# Page_5_DDR.net
KiCad netlist of a schematic drawn in Altium Designer
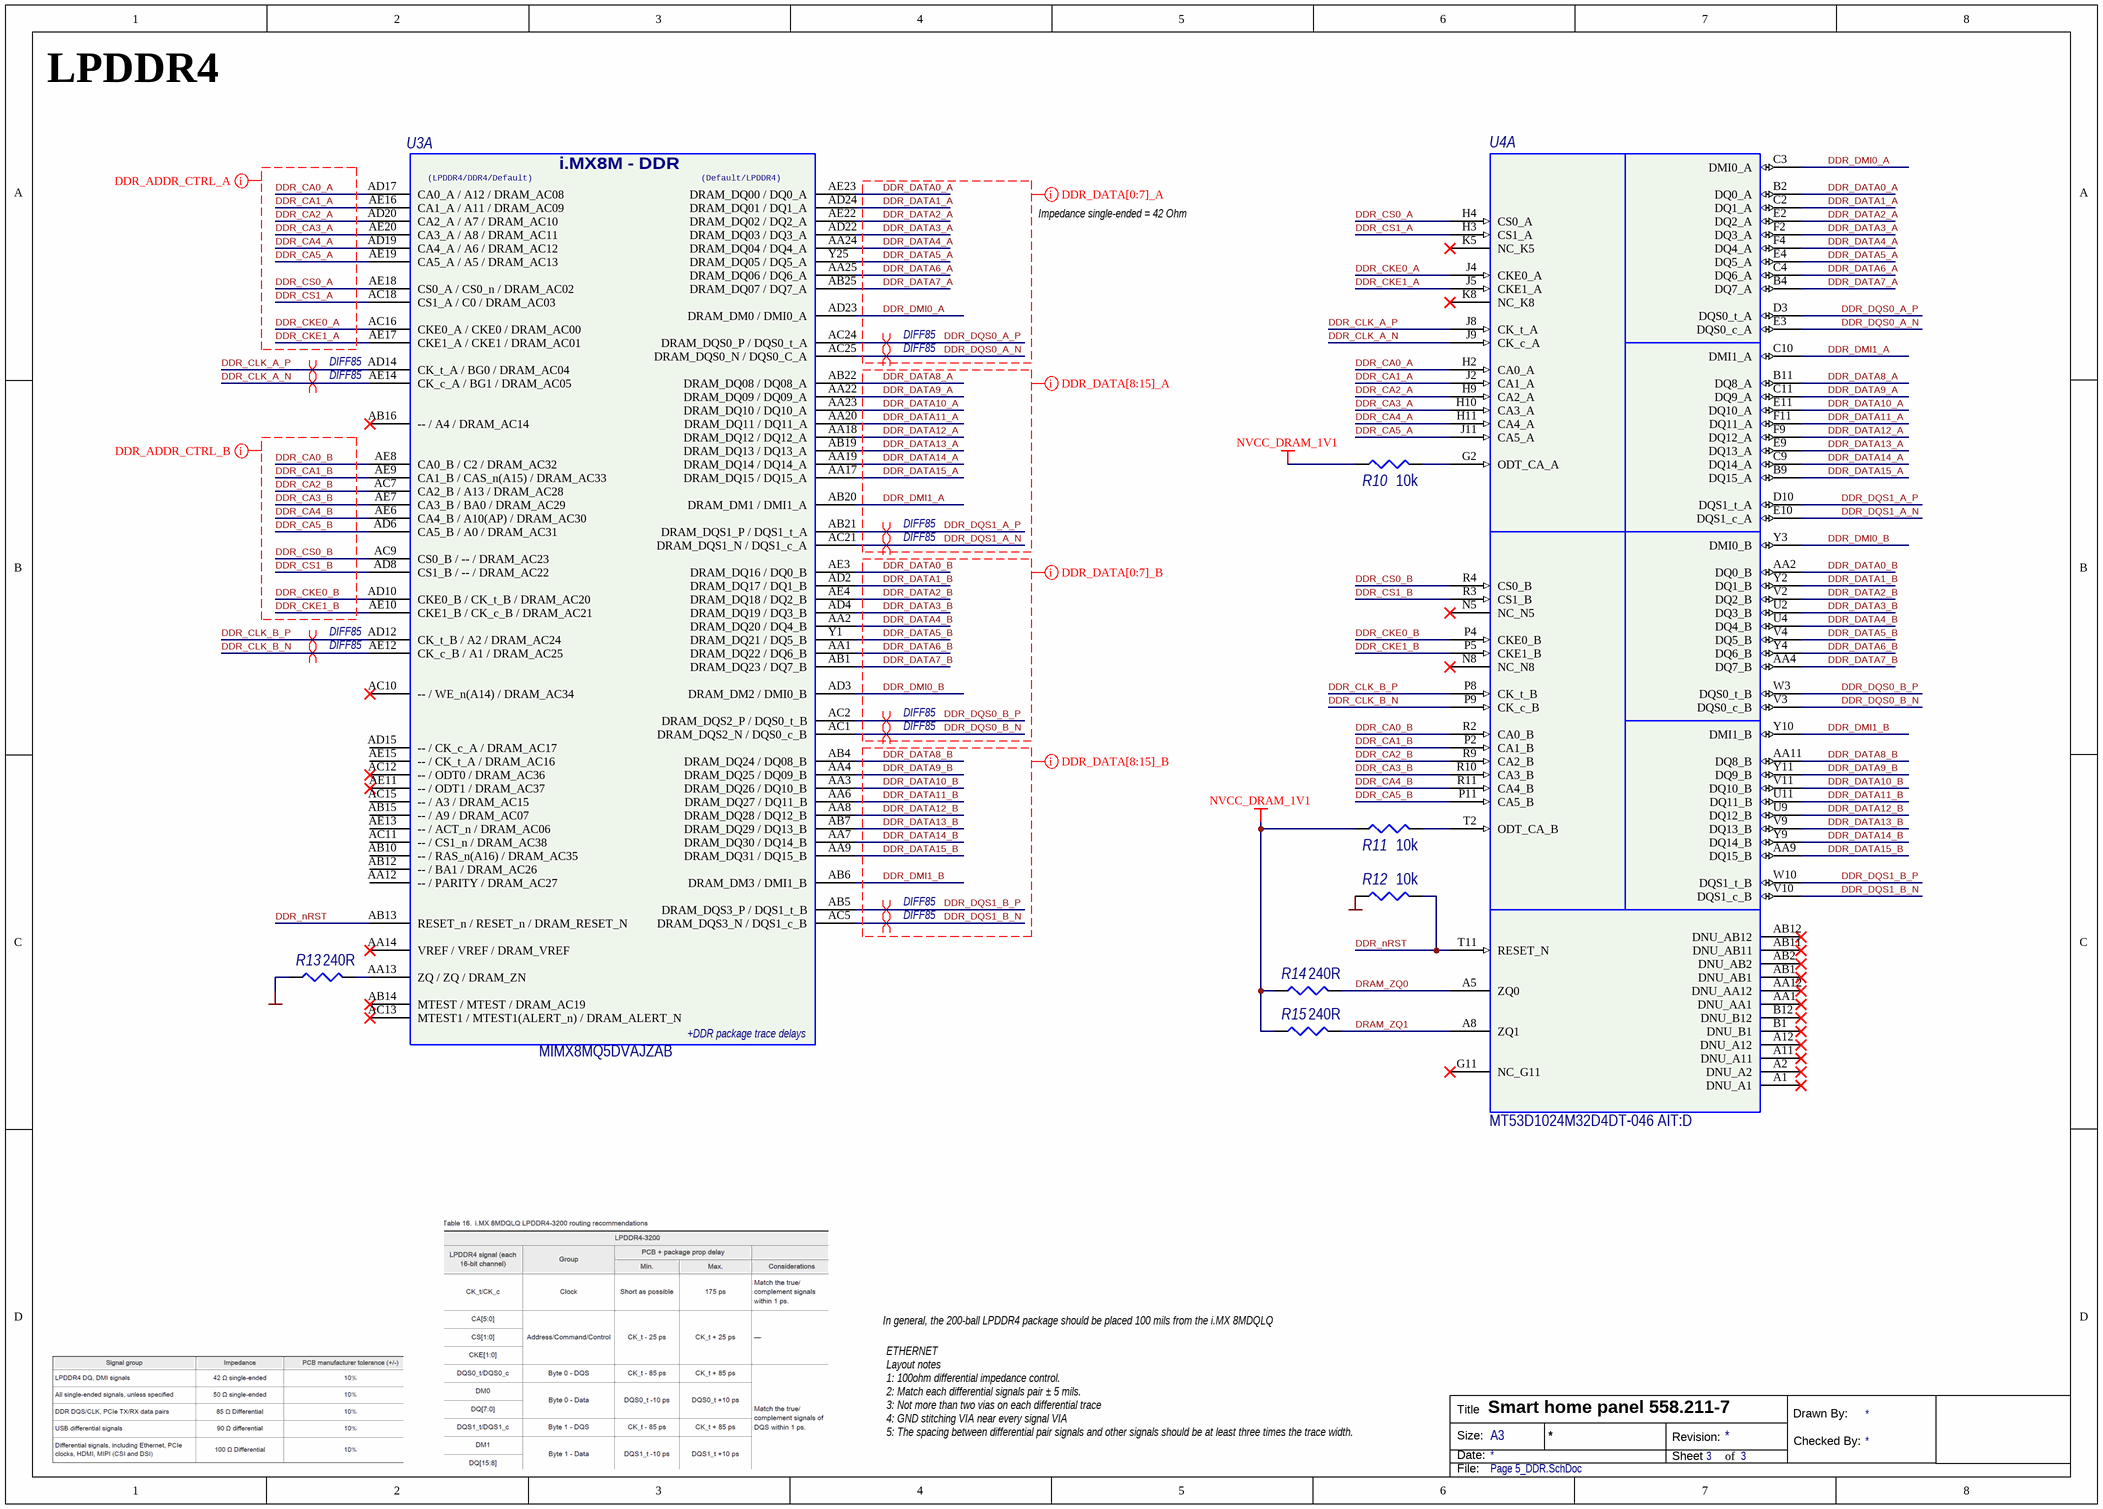
[diagram p0: Page 5_DDR.SchDoc]

(export (version "E")
  (design (tool "Eeschema 10.0.6"))
  (components
    (comp (ref "R10")
      (value "10k")
      (footprint "R0402_L_R")
      (description "RES 10.0K OHM 1/16W 1% 0402")
      (fields
        (field (name "MANUFACTURER") "Yageo")
        (field (name "MANUFACTURER PART NUMBER") "RC0402FR-0710KL")
      )
      (libsource (lib "R0402") (part "RC0402FR-0710KL"))
    )
    (comp (ref "R11")
      (value "10k")
      (footprint "R0402_L_R")
      (description "RES 10.0K OHM 1/16W 1% 0402")
      (fields
        (field (name "MANUFACTURER") "Yageo")
        (field (name "MANUFACTURER PART NUMBER") "RC0402FR-0710KL")
      )
      (libsource (lib "R0402") (part "RC0402FR-0710KL"))
    )
    (comp (ref "R12")
      (value "10k")
      (footprint "R0402_L_R")
      (description "RES 10.0K OHM 1/16W 1% 0402")
      (fields
        (field (name "MANUFACTURER") "Yageo")
        (field (name "MANUFACTURER PART NUMBER") "RC0402FR-0710KL")
      )
      (libsource (lib "R0402") (part "RC0402FR-0710KL"))
    )
    (comp (ref "R13")
      (value "240R")
      (footprint "R0402_L_R")
      (description "RES 240 OHM 1/16W 1% 0402 ±100ppm")
      (fields
        (field (name "MANUFACTURER") "Yageo")
        (field (name "MANUFACTURER PART NUMBER") "RC0402FR-07240RL")
      )
      (libsource (lib "R0402") (part "RC0402FR-07240RL"))
    )
    (comp (ref "R14")
      (value "240R")
      (footprint "R0402_L_R")
      (description "RES 240 OHM 1/16W 1% 0402 ±100ppm")
      (fields
        (field (name "MANUFACTURER") "Yageo")
        (field (name "MANUFACTURER PART NUMBER") "RC0402FR-07240RL")
      )
      (libsource (lib "R0402") (part "RC0402FR-07240RL"))
    )
    (comp (ref "R15")
      (value "240R")
      (footprint "R0402_L_R")
      (description "RES 240 OHM 1/16W 1% 0402 ±100ppm")
      (fields
        (field (name "MANUFACTURER") "Yageo")
        (field (name "MANUFACTURER PART NUMBER") "RC0402FR-07240RL")
      )
      (libsource (lib "R0402") (part "RC0402FR-07240RL"))
    )
    (comp (ref "U3")
      (value "MIMX8MQ5DVAJZAB")
      (footprint "FCPBGA-621_NXP")
      (description "ARM Cortex-A53 Microprocessor IC i.MX8MQ 4 Core, 64-Bit 1.5GHz 621-FCPBGA (17x17)")
      (fields (field (name "MANUFACTURER") "NXP Semiconductors"))
      (libsource (lib "MCU") (part "I.MX8MQ5DVAJZAB"))
    )
    (comp (ref "U4")
      (value "MT53D1024M32D4DT-046 AIT:D")
      (footprint "VFBGA200_10x14x0.95")
      (description "DRAM Chip LPDDR4 SDRAM 32Gbit 1024M X 32 200-Ball VFBGA")
      (fields (field (name "MANUFACTURER") "Micron Technology"))
      (libsource (lib "IC_Memory") (part "MT53D1024M32D4DT"))
    )
  )
  (nets
    (net (code "1") (name "/DDR_CA0_A") (class "Default")
      (node (ref "U3") (pin "AD17") (pinfunction "CA0_A_/_A12_/_DRAM_AC08_AD17") (pintype "passive"))
      (node (ref "U4") (pin "H2") (pinfunction "CA0_A_H2") (pintype "input"))
    )
    (net (code "2") (name "/DDR_CA0_B") (class "Default")
      (node (ref "U3") (pin "AE8") (pinfunction "CA0_B_/_C2_/_DRAM_AC32_AE8") (pintype "passive"))
      (node (ref "U4") (pin "R2") (pinfunction "CA0_B_R2") (pintype "input"))
    )
    (net (code "3") (name "/DDR_CA1_A") (class "Default")
      (node (ref "U3") (pin "AE16") (pinfunction "CA1_A_/_A11_/_DRAM_AC09_AE16") (pintype "passive"))
      (node (ref "U4") (pin "J2") (pinfunction "CA1_A_J2") (pintype "input"))
    )
    (net (code "4") (name "/DDR_CA1_B") (class "Default")
      (node (ref "U3") (pin "AE9") (pinfunction "CA1_B_/_CAS_n(A15)_/_DRAM_AC33_AE9") (pintype "passive"))
      (node (ref "U4") (pin "P2") (pinfunction "CA1_B_P2") (pintype "input"))
    )
    (net (code "5") (name "/DDR_CA2_A") (class "Default")
      (node (ref "U3") (pin "AD20") (pinfunction "CA2_A_/_A7_/_DRAM_AC10_AD20") (pintype "passive"))
      (node (ref "U4") (pin "H9") (pinfunction "CA2_A_H9") (pintype "input"))
    )
    (net (code "6") (name "/DDR_CA2_B") (class "Default")
      (node (ref "U3") (pin "AC7") (pinfunction "CA2_B_/_A13_/_DRAM_AC28_AC7") (pintype "passive"))
      (node (ref "U4") (pin "R9") (pinfunction "CA2_B_R9") (pintype "input"))
    )
    (net (code "7") (name "/DDR_CA3_A") (class "Default")
      (node (ref "U3") (pin "AE20") (pinfunction "CA3_A_/_A8_/_DRAM_AC11_AE20") (pintype "passive"))
      (node (ref "U4") (pin "H10") (pinfunction "CA3_A_H10") (pintype "input"))
    )
    (net (code "8") (name "/DDR_CA3_B") (class "Default")
      (node (ref "U3") (pin "AE7") (pinfunction "CA3_B_/_BA0_/_DRAM_AC29_AE7") (pintype "passive"))
      (node (ref "U4") (pin "R10") (pinfunction "CA3_B_R10") (pintype "input"))
    )
    (net (code "9") (name "/DDR_CA4_A") (class "Default")
      (node (ref "U3") (pin "AD19") (pinfunction "CA4_A_/_A6_/_DRAM_AC12_AD19") (pintype "passive"))
      (node (ref "U4") (pin "H11") (pinfunction "CA4_A_H11") (pintype "input"))
    )
    (net (code "10") (name "/DDR_CA4_B") (class "Default")
      (node (ref "U3") (pin "AE6") (pinfunction "CA4_B_/_A10(AP)_/_DRAM_AC30_AE6") (pintype "passive"))
      (node (ref "U4") (pin "R11") (pinfunction "CA4_B_R11") (pintype "input"))
    )
    (net (code "11") (name "/DDR_CA5_A") (class "Default")
      (node (ref "U3") (pin "AE19") (pinfunction "CA5_A_/_A5_/_DRAM_AC13_AE19") (pintype "passive"))
      (node (ref "U4") (pin "J11") (pinfunction "CA5_A_J11") (pintype "input"))
    )
    (net (code "12") (name "/DDR_CA5_B") (class "Default")
      (node (ref "U3") (pin "AD6") (pinfunction "CA5_B_/_A0_/_DRAM_AC31_AD6") (pintype "passive"))
      (node (ref "U4") (pin "P11") (pinfunction "CA5_B_P11") (pintype "input"))
    )
    (net (code "13") (name "/DDR_CKE0_A") (class "Default")
      (node (ref "U3") (pin "AC16") (pinfunction "CKE0_A_/_CKE0_/_DRAM_AC00_AC16") (pintype "passive"))
      (node (ref "U4") (pin "J4") (pinfunction "CKE0_A_J4") (pintype "input"))
    )
    (net (code "14") (name "/DDR_CKE0_B") (class "Default")
      (node (ref "U3") (pin "AD10") (pinfunction "CKE0_B_/_CK_t_B_/_DRAM_AC20_AD10") (pintype "passive"))
      (node (ref "U4") (pin "P4") (pinfunction "CKE0_B_P4") (pintype "input"))
    )
    (net (code "15") (name "/DDR_CKE1_A") (class "Default")
      (node (ref "U3") (pin "AE17") (pinfunction "CKE1_A_/_CKE1_/_DRAM_AC01_AE17") (pintype "passive"))
      (node (ref "U4") (pin "J5") (pinfunction "CKE1_A_J5") (pintype "input"))
    )
    (net (code "16") (name "/DDR_CKE1_B") (class "Default")
      (node (ref "U3") (pin "AE10") (pinfunction "CKE1_B_/_CK_c_B_/_DRAM_AC21_AE10") (pintype "passive"))
      (node (ref "U4") (pin "P5") (pinfunction "CKE1_B_P5") (pintype "input"))
    )
    (net (code "17") (name "/DDR_CLK_A_N") (class "Default")
      (node (ref "U3") (pin "AE14") (pinfunction "CK_c_A_/_BG1_/_DRAM_AC05_AE14") (pintype "passive"))
      (node (ref "U4") (pin "J9") (pinfunction "CK_c_A_J9") (pintype "input"))
    )
    (net (code "18") (name "/DDR_CLK_A_P") (class "Default")
      (node (ref "U3") (pin "AD14") (pinfunction "CK_t_A_/_BG0_/_DRAM_AC04_AD14") (pintype "passive"))
      (node (ref "U4") (pin "J8") (pinfunction "CK_t_A_J8") (pintype "input"))
    )
    (net (code "19") (name "/DDR_CLK_B_N") (class "Default")
      (node (ref "U3") (pin "AE12") (pinfunction "CK_c_B_/_A1_/_DRAM_AC25_AE12") (pintype "passive"))
      (node (ref "U4") (pin "P9") (pinfunction "CK_c_B_P9") (pintype "input"))
    )
    (net (code "20") (name "/DDR_CLK_B_P") (class "Default")
      (node (ref "U3") (pin "AD12") (pinfunction "CK_t_B_/_A2_/_DRAM_AC24_AD12") (pintype "passive"))
      (node (ref "U4") (pin "P8") (pinfunction "CK_t_B_P8") (pintype "input"))
    )
    (net (code "21") (name "/DDR_CS0_A") (class "Default")
      (node (ref "U3") (pin "AE18") (pinfunction "CS0_A_/_CS0_n_/_DRAM_AC02_AE18") (pintype "passive"))
      (node (ref "U4") (pin "H4") (pinfunction "CS0_A_H4") (pintype "input"))
    )
    (net (code "22") (name "/DDR_CS0_B") (class "Default")
      (node (ref "U3") (pin "AC9") (pinfunction "CS0_B_/_--_/_DRAM_AC23_AC9") (pintype "passive"))
      (node (ref "U4") (pin "R4") (pinfunction "CS0_B_R4") (pintype "input"))
    )
    (net (code "23") (name "/DDR_CS1_A") (class "Default")
      (node (ref "U3") (pin "AC18") (pinfunction "CS1_A_/_C0_/_DRAM_AC03_AC18") (pintype "passive"))
      (node (ref "U4") (pin "H3") (pinfunction "CS1_A_H3") (pintype "input"))
    )
    (net (code "24") (name "/DDR_CS1_B") (class "Default")
      (node (ref "U3") (pin "AD8") (pinfunction "CS1_B_/_--_/_DRAM_AC22_AD8") (pintype "passive"))
      (node (ref "U4") (pin "R3") (pinfunction "CS1_B_R3") (pintype "input"))
    )
    (net (code "25") (name "/DDR_DATA0_A") (class "Default")
      (node (ref "U3") (pin "AE23") (pinfunction "DRAM_DQ00_/_DQ0_A_AE23") (pintype "passive"))
      (node (ref "U4") (pin "B2") (pinfunction "DQ0_A_B2") (pintype "bidirectional"))
    )
    (net (code "26") (name "/DDR_DATA0_B") (class "Default")
      (node (ref "U3") (pin "AE3") (pinfunction "DRAM_DQ16_/_DQ0_B_AE3") (pintype "passive"))
      (node (ref "U4") (pin "AA2") (pinfunction "DQ0_B_AA2") (pintype "bidirectional"))
    )
    (net (code "27") (name "/DDR_DATA1_A") (class "Default")
      (node (ref "U3") (pin "AD24") (pinfunction "DRAM_DQ01_/_DQ1_A_AD24") (pintype "passive"))
      (node (ref "U4") (pin "C2") (pinfunction "DQ1_A_C2") (pintype "bidirectional"))
    )
    (net (code "28") (name "/DDR_DATA1_B") (class "Default")
      (node (ref "U3") (pin "AD2") (pinfunction "DRAM_DQ17_/_DQ1_B_AD2") (pintype "passive"))
      (node (ref "U4") (pin "Y2") (pinfunction "DQ1_B_Y2") (pintype "bidirectional"))
    )
    (net (code "29") (name "/DDR_DATA2_A") (class "Default")
      (node (ref "U3") (pin "AE22") (pinfunction "DRAM_DQ02_/_DQ2_A_AE22") (pintype "passive"))
      (node (ref "U4") (pin "E2") (pinfunction "DQ2_A_E2") (pintype "bidirectional"))
    )
    (net (code "30") (name "/DDR_DATA2_B") (class "Default")
      (node (ref "U3") (pin "AE4") (pinfunction "DRAM_DQ18_/_DQ2_B_AE4") (pintype "passive"))
      (node (ref "U4") (pin "V2") (pinfunction "DQ2_B_V2") (pintype "bidirectional"))
    )
    (net (code "31") (name "/DDR_DATA3_A") (class "Default")
      (node (ref "U3") (pin "AD22") (pinfunction "DRAM_DQ03_/_DQ3_A_AD22") (pintype "passive"))
      (node (ref "U4") (pin "F2") (pinfunction "DQ3_A_F2") (pintype "bidirectional"))
    )
    (net (code "32") (name "/DDR_DATA3_B") (class "Default")
      (node (ref "U3") (pin "AD4") (pinfunction "DRAM_DQ19_/_DQ3_B_AD4") (pintype "passive"))
      (node (ref "U4") (pin "U2") (pinfunction "DQ3_B_U2") (pintype "bidirectional"))
    )
    (net (code "33") (name "/DDR_DATA4_A") (class "Default")
      (node (ref "U3") (pin "AA24") (pinfunction "DRAM_DQ04_/_DQ4_A_AA24") (pintype "passive"))
      (node (ref "U4") (pin "F4") (pinfunction "DQ4_A_F4") (pintype "bidirectional"))
    )
    (net (code "34") (name "/DDR_DATA4_B") (class "Default")
      (node (ref "U3") (pin "AA2") (pinfunction "DRAM_DQ20_/_DQ4_B_AA2") (pintype "passive"))
      (node (ref "U4") (pin "U4") (pinfunction "DQ4_B_U4") (pintype "bidirectional"))
    )
    (net (code "35") (name "/DDR_DATA5_A") (class "Default")
      (node (ref "U3") (pin "Y25") (pinfunction "DRAM_DQ05_/_DQ5_A_Y25") (pintype "passive"))
      (node (ref "U4") (pin "E4") (pinfunction "DQ5_A_E4") (pintype "bidirectional"))
    )
    (net (code "36") (name "/DDR_DATA5_B") (class "Default")
      (node (ref "U3") (pin "Y1") (pinfunction "DRAM_DQ21_/_DQ5_B_Y1") (pintype "passive"))
      (node (ref "U4") (pin "V4") (pinfunction "DQ5_B_V4") (pintype "bidirectional"))
    )
    (net (code "37") (name "/DDR_DATA6_A") (class "Default")
      (node (ref "U3") (pin "AA25") (pinfunction "DRAM_DQ06_/_DQ6_A_AA25") (pintype "passive"))
      (node (ref "U4") (pin "C4") (pinfunction "DQ6_A_C4") (pintype "bidirectional"))
    )
    (net (code "38") (name "/DDR_DATA6_B") (class "Default")
      (node (ref "U3") (pin "AA1") (pinfunction "DRAM_DQ22_/_DQ6_B_AA1") (pintype "passive"))
      (node (ref "U4") (pin "Y4") (pinfunction "DQ6_B_Y4") (pintype "bidirectional"))
    )
    (net (code "39") (name "/DDR_DATA7_A") (class "Default")
      (node (ref "U3") (pin "AB25") (pinfunction "DRAM_DQ07_/_DQ7_A_AB25") (pintype "passive"))
      (node (ref "U4") (pin "B4") (pinfunction "DQ7_A_B4") (pintype "bidirectional"))
    )
    (net (code "40") (name "/DDR_DATA7_B") (class "Default")
      (node (ref "U3") (pin "AB1") (pinfunction "DRAM_DQ23_/_DQ7_B_AB1") (pintype "passive"))
      (node (ref "U4") (pin "AA4") (pinfunction "DQ7_B_AA4") (pintype "bidirectional"))
    )
    (net (code "41") (name "/DDR_DATA8_A") (class "Default")
      (node (ref "U3") (pin "AB22") (pinfunction "DRAM_DQ08_/_DQ08_A_AB22") (pintype "passive"))
      (node (ref "U4") (pin "B11") (pinfunction "DQ8_A_B11") (pintype "bidirectional"))
    )
    (net (code "42") (name "/DDR_DATA8_B") (class "Default")
      (node (ref "U3") (pin "AB4") (pinfunction "DRAM_DQ24_/_DQ08_B_AB4") (pintype "passive"))
      (node (ref "U4") (pin "AA11") (pinfunction "DQ8_B_AA11") (pintype "bidirectional"))
    )
    (net (code "43") (name "/DDR_DATA9_A") (class "Default")
      (node (ref "U3") (pin "AA22") (pinfunction "DRAM_DQ09_/_DQ09_A_AA22") (pintype "passive"))
      (node (ref "U4") (pin "C11") (pinfunction "DQ9_A_C11") (pintype "bidirectional"))
    )
    (net (code "44") (name "/DDR_DATA9_B") (class "Default")
      (node (ref "U3") (pin "AA4") (pinfunction "DRAM_DQ25_/_DQ09_B_AA4") (pintype "passive"))
      (node (ref "U4") (pin "Y11") (pinfunction "DQ9_B_Y11") (pintype "bidirectional"))
    )
    (net (code "45") (name "/DDR_DATA10_A") (class "Default")
      (node (ref "U3") (pin "AA23") (pinfunction "DRAM_DQ10_/_DQ10_A_AA23") (pintype "passive"))
      (node (ref "U4") (pin "E11") (pinfunction "DQ10_A_E11") (pintype "bidirectional"))
    )
    (net (code "46") (name "/DDR_DATA10_B") (class "Default")
      (node (ref "U3") (pin "AA3") (pinfunction "DRAM_DQ26_/_DQ10_B_AA3") (pintype "passive"))
      (node (ref "U4") (pin "V11") (pinfunction "DQ10_B_V11") (pintype "bidirectional"))
    )
    (net (code "47") (name "/DDR_DATA11_A") (class "Default")
      (node (ref "U3") (pin "AA20") (pinfunction "DRAM_DQ11_/_DQ11_A_AA20") (pintype "passive"))
      (node (ref "U4") (pin "F11") (pinfunction "DQ11_A_F11") (pintype "bidirectional"))
    )
    (net (code "48") (name "/DDR_DATA11_B") (class "Default")
      (node (ref "U3") (pin "AA6") (pinfunction "DRAM_DQ27_/_DQ11_B_AA6") (pintype "passive"))
      (node (ref "U4") (pin "U11") (pinfunction "DQ11_B_U11") (pintype "bidirectional"))
    )
    (net (code "49") (name "/DDR_DATA12_A") (class "Default")
      (node (ref "U3") (pin "AA18") (pinfunction "DRAM_DQ12_/_DQ12_A_AA18") (pintype "passive"))
      (node (ref "U4") (pin "F9") (pinfunction "DQ12_A_F9") (pintype "bidirectional"))
    )
    (net (code "50") (name "/DDR_DATA12_B") (class "Default")
      (node (ref "U3") (pin "AA8") (pinfunction "DRAM_DQ28_/_DQ12_B_AA8") (pintype "passive"))
      (node (ref "U4") (pin "U9") (pinfunction "DQ12_B_U9") (pintype "bidirectional"))
    )
    (net (code "51") (name "/DDR_DATA13_A") (class "Default")
      (node (ref "U3") (pin "AB19") (pinfunction "DRAM_DQ13_/_DQ13_A_AB19") (pintype "passive"))
      (node (ref "U4") (pin "E9") (pinfunction "DQ13_A_E9") (pintype "bidirectional"))
    )
    (net (code "52") (name "/DDR_DATA13_B") (class "Default")
      (node (ref "U3") (pin "AB7") (pinfunction "DRAM_DQ29_/_DQ13_B_AB7") (pintype "passive"))
      (node (ref "U4") (pin "V9") (pinfunction "DQ13_B_V9") (pintype "bidirectional"))
    )
    (net (code "53") (name "/DDR_DATA14_A") (class "Default")
      (node (ref "U3") (pin "AA19") (pinfunction "DRAM_DQ14_/_DQ14_A_AA19") (pintype "passive"))
      (node (ref "U4") (pin "C9") (pinfunction "DQ14_A_C9") (pintype "bidirectional"))
    )
    (net (code "54") (name "/DDR_DATA14_B") (class "Default")
      (node (ref "U3") (pin "AA7") (pinfunction "DRAM_DQ30_/_DQ14_B_AA7") (pintype "passive"))
      (node (ref "U4") (pin "Y9") (pinfunction "DQ14_B_Y9") (pintype "bidirectional"))
    )
    (net (code "55") (name "/DDR_DATA15_A") (class "Default")
      (node (ref "U3") (pin "AA17") (pinfunction "DRAM_DQ15_/_DQ15_A_AA17") (pintype "passive"))
      (node (ref "U4") (pin "B9") (pinfunction "DQ15_A_B9") (pintype "bidirectional"))
    )
    (net (code "56") (name "/DDR_DATA15_B") (class "Default")
      (node (ref "U3") (pin "AA9") (pinfunction "DRAM_DQ31_/_DQ15_B_AA9") (pintype "passive"))
      (node (ref "U4") (pin "AA9") (pinfunction "DQ15_B_AA9") (pintype "bidirectional"))
    )
    (net (code "57") (name "/DDR_DMI0_A") (class "Default")
      (node (ref "U3") (pin "AD23") (pinfunction "DRAM_DM0_/_DMI0_A_AD23") (pintype "passive"))
      (node (ref "U4") (pin "C3") (pinfunction "DMI0_A_C3") (pintype "bidirectional"))
    )
    (net (code "58") (name "/DDR_DMI0_B") (class "Default")
      (node (ref "U3") (pin "AD3") (pinfunction "DRAM_DM2_/_DMI0_B_AD3") (pintype "passive"))
      (node (ref "U4") (pin "Y3") (pinfunction "DMI0_B_Y3") (pintype "bidirectional"))
    )
    (net (code "59") (name "/DDR_DMI1_A") (class "Default")
      (node (ref "U3") (pin "AB20") (pinfunction "DRAM_DM1_/_DMI1_A_AB20") (pintype "passive"))
      (node (ref "U4") (pin "C10") (pinfunction "DMI1_A_C10") (pintype "bidirectional"))
    )
    (net (code "60") (name "/DDR_DMI1_B") (class "Default")
      (node (ref "U3") (pin "AB6") (pinfunction "DRAM_DM3_/_DMI1_B_AB6") (pintype "passive"))
      (node (ref "U4") (pin "Y10") (pinfunction "DMI1_B_Y10") (pintype "bidirectional"))
    )
    (net (code "61") (name "/DDR_DQS0_A_N") (class "Default")
      (node (ref "U3") (pin "AC25") (pinfunction "DRAM_DQS0_N_/_DQS0_C_A_AC25") (pintype "passive"))
      (node (ref "U4") (pin "E3") (pinfunction "DQS0_c_A_E3") (pintype "bidirectional"))
    )
    (net (code "62") (name "/DDR_DQS0_A_P") (class "Default")
      (node (ref "U3") (pin "AC24") (pinfunction "DRAM_DQS0_P_/_DQS0_t_A_AC24") (pintype "passive"))
      (node (ref "U4") (pin "D3") (pinfunction "DQS0_t_A_D3") (pintype "bidirectional"))
    )
    (net (code "63") (name "/DDR_DQS0_B_N") (class "Default")
      (node (ref "U3") (pin "AC1") (pinfunction "DRAM_DQS2_N_/_DQS0_c_B_AC1") (pintype "passive"))
      (node (ref "U4") (pin "V3") (pinfunction "DQS0_c_B_V3") (pintype "bidirectional"))
    )
    (net (code "64") (name "/DDR_DQS0_B_P") (class "Default")
      (node (ref "U3") (pin "AC2") (pinfunction "DRAM_DQS2_P_/_DQS0_t_B_AC2") (pintype "passive"))
      (node (ref "U4") (pin "W3") (pinfunction "DQS0_t_B_W3") (pintype "bidirectional"))
    )
    (net (code "65") (name "/DDR_DQS1_A_N") (class "Default")
      (node (ref "U3") (pin "AC21") (pinfunction "DRAM_DQS1_N_/_DQS1_c_A_AC21") (pintype "passive"))
      (node (ref "U4") (pin "E10") (pinfunction "DQS1_c_A_E10") (pintype "bidirectional"))
    )
    (net (code "66") (name "/DDR_DQS1_A_P") (class "Default")
      (node (ref "U3") (pin "AB21") (pinfunction "DRAM_DQS1_P_/_DQS1_t_A_AB21") (pintype "passive"))
      (node (ref "U4") (pin "D10") (pinfunction "DQS1_t_A_D10") (pintype "bidirectional"))
    )
    (net (code "67") (name "/DDR_DQS1_B_N") (class "Default")
      (node (ref "U3") (pin "AC5") (pinfunction "DRAM_DQS3_N_/_DQS1_c_B_AC5") (pintype "passive"))
      (node (ref "U4") (pin "V10") (pinfunction "DQS1_c_B_V10") (pintype "bidirectional"))
    )
    (net (code "68") (name "/DDR_DQS1_B_P") (class "Default")
      (node (ref "U3") (pin "AB5") (pinfunction "DRAM_DQS3_P_/_DQS1_t_B_AB5") (pintype "passive"))
      (node (ref "U4") (pin "W10") (pinfunction "DQS1_t_B_W10") (pintype "bidirectional"))
    )
    (net (code "69") (name "/DDR_nRST") (class "Default")
      (node (ref "R12") (pin "2") (pinfunction "2_2") (pintype "passive"))
      (node (ref "U3") (pin "AB13") (pinfunction "RESET_n_/_RESET_n_/_DRAM_RESET_N_AB13") (pintype "passive"))
      (node (ref "U4") (pin "T11") (pinfunction "RESET_N_T11") (pintype "input"))
    )
    (net (code "70") (name "/DRAM_ZQ0") (class "Default")
      (node (ref "R14") (pin "2") (pinfunction "2_2") (pintype "passive"))
      (node (ref "U4") (pin "A5") (pinfunction "ZQ0_A5") (pintype "passive"))
    )
    (net (code "71") (name "/DRAM_ZQ1") (class "Default")
      (node (ref "R15") (pin "2") (pinfunction "2_2") (pintype "passive"))
      (node (ref "U4") (pin "A8") (pinfunction "ZQ1_A8") (pintype "passive"))
    )
    (net (code "72") (name "0V") (class "Default")
      (node (ref "R12") (pin "1") (pinfunction "1_1") (pintype "passive"))
      (node (ref "R13") (pin "1") (pinfunction "1_1") (pintype "passive"))
    )
    (net (code "73") (name "NVCC_DRAM_1V1") (class "Default")
      (node (ref "R10") (pin "1") (pinfunction "1_1") (pintype "passive"))
      (node (ref "R11") (pin "1") (pinfunction "1_1") (pintype "passive"))
      (node (ref "R14") (pin "1") (pinfunction "1_1") (pintype "passive"))
      (node (ref "R15") (pin "1") (pinfunction "1_1") (pintype "passive"))
    )
    (net (code "74") (name "Net-(U3A-ZQ_{slash}_ZQ_{slash}_DRAM_ZN)") (class "Default")
      (node (ref "R13") (pin "2") (pinfunction "2_2") (pintype "passive"))
      (node (ref "U3") (pin "AA13") (pinfunction "ZQ_/_ZQ_/_DRAM_ZN_AA13") (pintype "passive"))
    )
    (net (code "75") (name "Net-(U4A-ODT_CA_A)") (class "Default")
      (node (ref "R10") (pin "2") (pinfunction "2_2") (pintype "passive"))
      (node (ref "U4") (pin "G2") (pinfunction "ODT_CA_A_G2") (pintype "input"))
    )
    (net (code "76") (name "Net-(U4A-ODT_CA_B)") (class "Default")
      (node (ref "R11") (pin "2") (pinfunction "2_2") (pintype "passive"))
      (node (ref "U4") (pin "T2") (pinfunction "ODT_CA_B_T2") (pintype "input"))
    )
    (net (code "77") (name "unconnected-(U3A---_{slash}_A3_{slash}_DRAM_AC15-PadAC15)") (class "Default")
      (node (ref "U3") (pin "AC15") (pinfunction "--_/_A3_/_DRAM_AC15_AC15") (pintype "passive"))
    )
    (net (code "78") (name "unconnected-(U3A---_{slash}_A4_{slash}_DRAM_AC14-PadAB16)") (class "Default")
      (node (ref "U3") (pin "AB16") (pinfunction "--_/_A4_/_DRAM_AC14_AB16") (pintype "passive+no_connect"))
    )
    (net (code "79") (name "unconnected-(U3A---_{slash}_A9_{slash}_DRAM_AC07-PadAB15)") (class "Default")
      (node (ref "U3") (pin "AB15") (pinfunction "--_/_A9_/_DRAM_AC07_AB15") (pintype "passive"))
    )
    (net (code "80") (name "unconnected-(U3A---_{slash}_ACT_n_{slash}_DRAM_AC06-PadAE13)") (class "Default")
      (node (ref "U3") (pin "AE13") (pinfunction "--_/_ACT_n_/_DRAM_AC06_AE13") (pintype "passive"))
    )
    (net (code "81") (name "unconnected-(U3A---_{slash}_BA1_{slash}_DRAM_AC26-PadAB12)") (class "Default")
      (node (ref "U3") (pin "AB12") (pinfunction "--_/_BA1_/_DRAM_AC26_AB12") (pintype "passive"))
    )
    (net (code "82") (name "unconnected-(U3A---_{slash}_CK_c_A_{slash}_DRAM_AC17-PadAD15)") (class "Default")
      (node (ref "U3") (pin "AD15") (pinfunction "--_/_CK_c_A_/_DRAM_AC17_AD15") (pintype "passive"))
    )
    (net (code "83") (name "unconnected-(U3A---_{slash}_CK_t_A_{slash}_DRAM_AC16-PadAE15)") (class "Default")
      (node (ref "U3") (pin "AE15") (pinfunction "--_/_CK_t_A_/_DRAM_AC16_AE15") (pintype "passive"))
    )
    (net (code "84") (name "unconnected-(U3A---_{slash}_CS1_n_{slash}_DRAM_AC38-PadAC11)") (class "Default")
      (node (ref "U3") (pin "AC11") (pinfunction "--_/_CS1_n_/_DRAM_AC38_AC11") (pintype "passive"))
    )
    (net (code "85") (name "unconnected-(U3A---_{slash}_ODT0_{slash}_DRAM_AC36-PadAC12)") (class "Default")
      (node (ref "U3") (pin "AC12") (pinfunction "--_/_ODT0_/_DRAM_AC36_AC12") (pintype "passive+no_connect"))
    )
    (net (code "86") (name "unconnected-(U3A---_{slash}_ODT1_{slash}_DRAM_AC37-PadAE11)") (class "Default")
      (node (ref "U3") (pin "AE11") (pinfunction "--_/_ODT1_/_DRAM_AC37_AE11") (pintype "passive+no_connect"))
    )
    (net (code "87") (name "unconnected-(U3A---_{slash}_PARITY_{slash}_DRAM_AC27-PadAA12)") (class "Default")
      (node (ref "U3") (pin "AA12") (pinfunction "--_/_PARITY_/_DRAM_AC27_AA12") (pintype "passive"))
    )
    (net (code "88") (name "unconnected-(U3A---_{slash}_RAS_n(A16)_{slash}_DRAM_AC35-PadAB10)") (class "Default")
      (node (ref "U3") (pin "AB10") (pinfunction "--_/_RAS_n(A16)_/_DRAM_AC35_AB10") (pintype "passive"))
    )
    (net (code "89") (name "unconnected-(U3A---_{slash}_WE_n(A14)_{slash}_DRAM_AC34-PadAC10)") (class "Default")
      (node (ref "U3") (pin "AC10") (pinfunction "--_/_WE_n(A14)_/_DRAM_AC34_AC10") (pintype "passive+no_connect"))
    )
    (net (code "90") (name "unconnected-(U3A-MTEST1_{slash}_MTEST1(ALERT_n)_{slash}_DRAM_ALERT_N-PadAC13)") (class "Default")
      (node (ref "U3") (pin "AC13") (pinfunction "MTEST1_/_MTEST1(ALERT_n)_/_DRAM_ALERT_N_AC13") (pintype "passive+no_connect"))
    )
    (net (code "91") (name "unconnected-(U3A-MTEST_{slash}_MTEST_{slash}_DRAM_AC19-PadAB14)") (class "Default")
      (node (ref "U3") (pin "AB14") (pinfunction "MTEST_/_MTEST_/_DRAM_AC19_AB14") (pintype "passive+no_connect"))
    )
    (net (code "92") (name "unconnected-(U3A-VREF_{slash}_VREF_{slash}_DRAM_VREF-PadAA14)") (class "Default")
      (node (ref "U3") (pin "AA14") (pinfunction "VREF_/_VREF_/_DRAM_VREF_AA14") (pintype "passive+no_connect"))
    )
    (net (code "93") (name "unconnected-(U4A-DNU_A1-PadA1)") (class "Default")
      (node (ref "U4") (pin "A1") (pinfunction "DNU_A1_A1") (pintype "passive+no_connect"))
    )
    (net (code "94") (name "unconnected-(U4A-DNU_A2-PadA2)") (class "Default")
      (node (ref "U4") (pin "A2") (pinfunction "DNU_A2_A2") (pintype "passive+no_connect"))
    )
    (net (code "95") (name "unconnected-(U4A-DNU_A11-PadA11)") (class "Default")
      (node (ref "U4") (pin "A11") (pinfunction "DNU_A11_A11") (pintype "passive+no_connect"))
    )
    (net (code "96") (name "unconnected-(U4A-DNU_A12-PadA12)") (class "Default")
      (node (ref "U4") (pin "A12") (pinfunction "DNU_A12_A12") (pintype "passive+no_connect"))
    )
    (net (code "97") (name "unconnected-(U4A-DNU_AA1-PadAA1)") (class "Default")
      (node (ref "U4") (pin "AA1") (pinfunction "DNU_AA1_AA1") (pintype "passive+no_connect"))
    )
    (net (code "98") (name "unconnected-(U4A-DNU_AA12-PadAA12)") (class "Default")
      (node (ref "U4") (pin "AA12") (pinfunction "DNU_AA12_AA12") (pintype "passive+no_connect"))
    )
    (net (code "99") (name "unconnected-(U4A-DNU_AB1-PadAB1)") (class "Default")
      (node (ref "U4") (pin "AB1") (pinfunction "DNU_AB1_AB1") (pintype "passive+no_connect"))
    )
    (net (code "100") (name "unconnected-(U4A-DNU_AB2-PadAB2)") (class "Default")
      (node (ref "U4") (pin "AB2") (pinfunction "DNU_AB2_AB2") (pintype "passive+no_connect"))
    )
    (net (code "101") (name "unconnected-(U4A-DNU_AB11-PadAB11)") (class "Default")
      (node (ref "U4") (pin "AB11") (pinfunction "DNU_AB11_AB11") (pintype "passive+no_connect"))
    )
    (net (code "102") (name "unconnected-(U4A-DNU_AB12-PadAB12)") (class "Default")
      (node (ref "U4") (pin "AB12") (pinfunction "DNU_AB12_AB12") (pintype "passive+no_connect"))
    )
    (net (code "103") (name "unconnected-(U4A-DNU_B1-PadB1)") (class "Default")
      (node (ref "U4") (pin "B1") (pinfunction "DNU_B1_B1") (pintype "passive+no_connect"))
    )
    (net (code "104") (name "unconnected-(U4A-DNU_B12-PadB12)") (class "Default")
      (node (ref "U4") (pin "B12") (pinfunction "DNU_B12_B12") (pintype "passive+no_connect"))
    )
    (net (code "105") (name "unconnected-(U4A-NC_G11-PadG11)") (class "Default")
      (node (ref "U4") (pin "G11") (pinfunction "NC_G11_G11") (pintype "passive+no_connect"))
    )
    (net (code "106") (name "unconnected-(U4A-NC_K5-PadK5)") (class "Default")
      (node (ref "U4") (pin "K5") (pinfunction "NC_K5_K5") (pintype "passive+no_connect"))
    )
    (net (code "107") (name "unconnected-(U4A-NC_K8-PadK8)") (class "Default")
      (node (ref "U4") (pin "K8") (pinfunction "NC_K8_K8") (pintype "passive+no_connect"))
    )
    (net (code "108") (name "unconnected-(U4A-NC_N5-PadN5)") (class "Default")
      (node (ref "U4") (pin "N5") (pinfunction "NC_N5_N5") (pintype "passive+no_connect"))
    )
    (net (code "109") (name "unconnected-(U4A-NC_N8-PadN8)") (class "Default")
      (node (ref "U4") (pin "N8") (pinfunction "NC_N8_N8") (pintype "passive+no_connect"))
    )
  )
)
